# 18-AM64x-07.net
KiCad netlist of a schematic drawn in Altium Designer
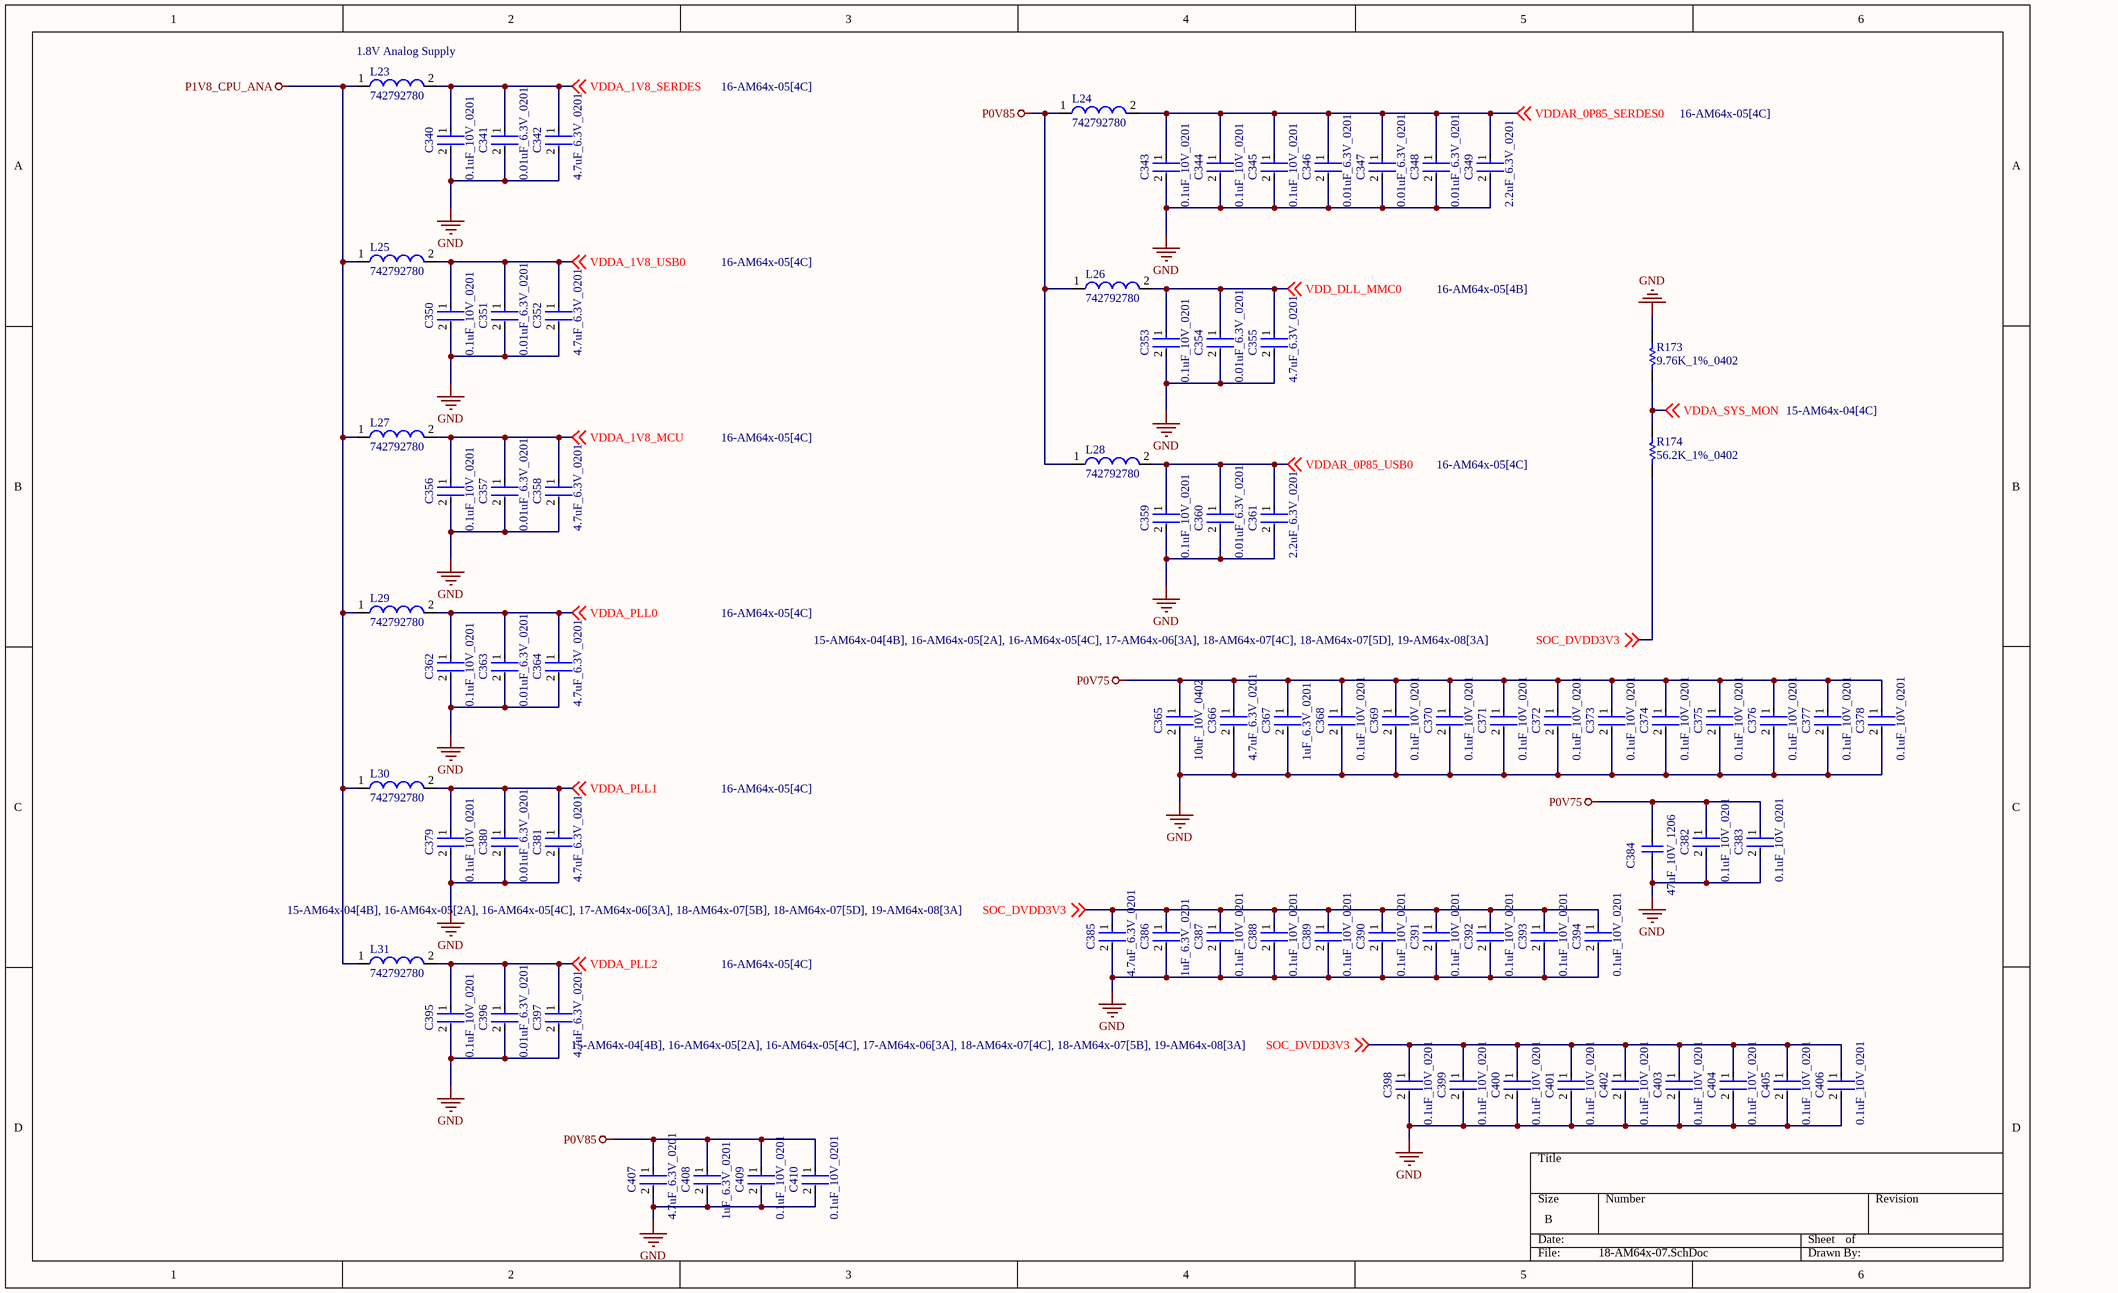
[diagram p0: 18-AM64x-07.SchDoc]

(export (version "E")
  (design (tool "Eeschema 10.0.6"))
  (components
    (comp (ref "C340")
      (value "0.1uF_10V_0201")
      (footprint "FP-GRM033-0_03-IPC_C")
      (description "Chip Multilayer Ceramic Capacitors for General Purpose, 0201, 0.10uF, X5R, 15%, 10%, 10V")
      (fields (field (name "TOLERANCE") "10%") (field (name "VOLTAGE") "10V"))
      (libsource (lib "Altium Content Vault") (part "b4654b650e69147ec39a6b967a45e02"))
    )
    (comp (ref "C341")
      (value "0.01uF_6.3V_0201")
      (footprint "FP-GRM033-0_03-IPC_A")
      (description "Chip Multilayer Ceramic Capacitors for General Purpose, 0201, 10000pF, X7R, 15%, 10%, 6.3V")
      (fields (field (name "TOLERANCE") "10%") (field (name "VOLTAGE") "6.3V"))
      (libsource (lib "Altium Content Vault") (part "b4654b650e69147ec39a6b967a45e02"))
    )
    (comp (ref "C342")
      (value "4.7uF_6.3V_0201")
      (footprint "FP-GRM035-0_09-IPC_B")
      (description "Chip Multilayer Ceramic Capacitors for General Purpose, 0201, 4.7uF, X5R, 15%, 20%, 6.3V")
      (fields (field (name "TOLERANCE") "20%"))
      (libsource (lib "Altium Content Vault") (part "02cd4be3c70576c341d710602a673aa"))
    )
    (comp (ref "C343")
      (value "0.1uF_10V_0201")
      (footprint "FP-GRM033-0_03-IPC_C")
      (description "Chip Multilayer Ceramic Capacitors for General Purpose, 0201, 0.10uF, X5R, 15%, 10%, 10V")
      (fields (field (name "TOLERANCE") "10%") (field (name "VOLTAGE") "10V"))
      (libsource (lib "Altium Content Vault") (part "b4654b650e69147ec39a6b967a45e02"))
    )
    (comp (ref "C344")
      (value "0.1uF_10V_0201")
      (footprint "FP-GRM033-0_03-IPC_C")
      (description "Chip Multilayer Ceramic Capacitors for General Purpose, 0201, 0.10uF, X5R, 15%, 10%, 10V")
      (fields (field (name "TOLERANCE") "10%") (field (name "VOLTAGE") "10V"))
      (libsource (lib "Altium Content Vault") (part "b4654b650e69147ec39a6b967a45e02"))
    )
    (comp (ref "C345")
      (value "0.1uF_10V_0201")
      (footprint "FP-GRM033-0_03-IPC_C")
      (description "Chip Multilayer Ceramic Capacitors for General Purpose, 0201, 0.10uF, X5R, 15%, 10%, 10V")
      (fields (field (name "TOLERANCE") "10%") (field (name "VOLTAGE") "10V"))
      (libsource (lib "Altium Content Vault") (part "b4654b650e69147ec39a6b967a45e02"))
    )
    (comp (ref "C346")
      (value "0.01uF_6.3V_0201")
      (footprint "FP-GRM033-0_03-IPC_A")
      (description "Chip Multilayer Ceramic Capacitors for General Purpose, 0201, 10000pF, X7R, 15%, 10%, 6.3V")
      (fields (field (name "TOLERANCE") "10%") (field (name "VOLTAGE") "6.3V"))
      (libsource (lib "Altium Content Vault") (part "b4654b650e69147ec39a6b967a45e02"))
    )
    (comp (ref "C347")
      (value "0.01uF_6.3V_0201")
      (footprint "FP-GRM033-0_03-IPC_A")
      (description "Chip Multilayer Ceramic Capacitors for General Purpose, 0201, 10000pF, X7R, 15%, 10%, 6.3V")
      (fields (field (name "TOLERANCE") "10%") (field (name "VOLTAGE") "6.3V"))
      (libsource (lib "Altium Content Vault") (part "b4654b650e69147ec39a6b967a45e02"))
    )
    (comp (ref "C348")
      (value "0.01uF_6.3V_0201")
      (footprint "FP-GRM033-0_03-IPC_A")
      (description "Chip Multilayer Ceramic Capacitors for General Purpose, 0201, 10000pF, X7R, 15%, 10%, 6.3V")
      (fields (field (name "TOLERANCE") "10%") (field (name "VOLTAGE") "6.3V"))
      (libsource (lib "Altium Content Vault") (part "b4654b650e69147ec39a6b967a45e02"))
    )
    (comp (ref "C349")
      (value "2.2uF_6.3V_0201")
      (footprint "FP-CL03-IPC_C")
      (description "Cap Ceramic 2.2uF 6.3V X5R ±20% Pad SMD 0201 +85°C T/R")
      (fields (field (name "TOLERANCE") "20%"))
      (libsource (lib "Altium Content Vault") (part "b4654b650e69147ec39a6b967a45e02"))
    )
    (comp (ref "C350")
      (value "0.1uF_10V_0201")
      (footprint "FP-GRM033-0_03-IPC_C")
      (description "Chip Multilayer Ceramic Capacitors for General Purpose, 0201, 0.10uF, X5R, 15%, 10%, 10V")
      (fields (field (name "TOLERANCE") "10%") (field (name "VOLTAGE") "10V"))
      (libsource (lib "Altium Content Vault") (part "b4654b650e69147ec39a6b967a45e02"))
    )
    (comp (ref "C351")
      (value "0.01uF_6.3V_0201")
      (footprint "FP-GRM033-0_03-IPC_A")
      (description "Chip Multilayer Ceramic Capacitors for General Purpose, 0201, 10000pF, X7R, 15%, 10%, 6.3V")
      (fields (field (name "TOLERANCE") "10%") (field (name "VOLTAGE") "6.3V"))
      (libsource (lib "Altium Content Vault") (part "b4654b650e69147ec39a6b967a45e02"))
    )
    (comp (ref "C352")
      (value "4.7uF_6.3V_0201")
      (footprint "FP-GRM035-0_09-IPC_B")
      (description "Chip Multilayer Ceramic Capacitors for General Purpose, 0201, 4.7uF, X5R, 15%, 20%, 6.3V")
      (fields (field (name "TOLERANCE") "20%"))
      (libsource (lib "Altium Content Vault") (part "02cd4be3c70576c341d710602a673aa"))
    )
    (comp (ref "C353")
      (value "0.1uF_10V_0201")
      (footprint "FP-GRM033-0_03-IPC_C")
      (description "Chip Multilayer Ceramic Capacitors for General Purpose, 0201, 0.10uF, X5R, 15%, 10%, 10V")
      (fields (field (name "TOLERANCE") "10%") (field (name "VOLTAGE") "10V"))
      (libsource (lib "Altium Content Vault") (part "b4654b650e69147ec39a6b967a45e02"))
    )
    (comp (ref "C354")
      (value "0.01uF_6.3V_0201")
      (footprint "FP-GRM033-0_03-IPC_A")
      (description "Chip Multilayer Ceramic Capacitors for General Purpose, 0201, 10000pF, X7R, 15%, 10%, 6.3V")
      (fields (field (name "TOLERANCE") "10%") (field (name "VOLTAGE") "6.3V"))
      (libsource (lib "Altium Content Vault") (part "b4654b650e69147ec39a6b967a45e02"))
    )
    (comp (ref "C355")
      (value "4.7uF_6.3V_0201")
      (footprint "FP-GRM035-0_09-IPC_B")
      (description "Chip Multilayer Ceramic Capacitors for General Purpose, 0201, 4.7uF, X5R, 15%, 20%, 6.3V")
      (fields (field (name "TOLERANCE") "20%"))
      (libsource (lib "Altium Content Vault") (part "02cd4be3c70576c341d710602a673aa"))
    )
    (comp (ref "C356")
      (value "0.1uF_10V_0201")
      (footprint "FP-GRM033-0_03-IPC_C")
      (description "Chip Multilayer Ceramic Capacitors for General Purpose, 0201, 0.10uF, X5R, 15%, 10%, 10V")
      (fields (field (name "TOLERANCE") "10%") (field (name "VOLTAGE") "10V"))
      (libsource (lib "Altium Content Vault") (part "b4654b650e69147ec39a6b967a45e02"))
    )
    (comp (ref "C357")
      (value "0.01uF_6.3V_0201")
      (footprint "FP-GRM033-0_03-IPC_A")
      (description "Chip Multilayer Ceramic Capacitors for General Purpose, 0201, 10000pF, X7R, 15%, 10%, 6.3V")
      (fields (field (name "TOLERANCE") "10%") (field (name "VOLTAGE") "6.3V"))
      (libsource (lib "Altium Content Vault") (part "b4654b650e69147ec39a6b967a45e02"))
    )
    (comp (ref "C358")
      (value "4.7uF_6.3V_0201")
      (footprint "FP-GRM035-0_09-IPC_B")
      (description "Chip Multilayer Ceramic Capacitors for General Purpose, 0201, 4.7uF, X5R, 15%, 20%, 6.3V")
      (fields (field (name "TOLERANCE") "20%"))
      (libsource (lib "Altium Content Vault") (part "02cd4be3c70576c341d710602a673aa"))
    )
    (comp (ref "C359")
      (value "0.1uF_10V_0201")
      (footprint "FP-GRM033-0_03-IPC_C")
      (description "Chip Multilayer Ceramic Capacitors for General Purpose, 0201, 0.10uF, X5R, 15%, 10%, 10V")
      (fields (field (name "TOLERANCE") "10%") (field (name "VOLTAGE") "10V"))
      (libsource (lib "Altium Content Vault") (part "b4654b650e69147ec39a6b967a45e02"))
    )
    (comp (ref "C360")
      (value "0.01uF_6.3V_0201")
      (footprint "FP-GRM033-0_03-IPC_A")
      (description "Chip Multilayer Ceramic Capacitors for General Purpose, 0201, 10000pF, X7R, 15%, 10%, 6.3V")
      (fields (field (name "TOLERANCE") "10%") (field (name "VOLTAGE") "6.3V"))
      (libsource (lib "Altium Content Vault") (part "b4654b650e69147ec39a6b967a45e02"))
    )
    (comp (ref "C361")
      (value "2.2uF_6.3V_0201")
      (footprint "FP-CL03-IPC_C")
      (description "Cap Ceramic 2.2uF 6.3V X5R ±20% Pad SMD 0201 +85°C T/R")
      (fields (field (name "TOLERANCE") "20%"))
      (libsource (lib "Altium Content Vault") (part "b4654b650e69147ec39a6b967a45e02"))
    )
    (comp (ref "C362")
      (value "0.1uF_10V_0201")
      (footprint "FP-GRM033-0_03-IPC_C")
      (description "Chip Multilayer Ceramic Capacitors for General Purpose, 0201, 0.10uF, X5R, 15%, 10%, 10V")
      (fields (field (name "TOLERANCE") "10%") (field (name "VOLTAGE") "10V"))
      (libsource (lib "Altium Content Vault") (part "b4654b650e69147ec39a6b967a45e02"))
    )
    (comp (ref "C363")
      (value "0.01uF_6.3V_0201")
      (footprint "FP-GRM033-0_03-IPC_A")
      (description "Chip Multilayer Ceramic Capacitors for General Purpose, 0201, 10000pF, X7R, 15%, 10%, 6.3V")
      (fields (field (name "TOLERANCE") "10%") (field (name "VOLTAGE") "6.3V"))
      (libsource (lib "Altium Content Vault") (part "b4654b650e69147ec39a6b967a45e02"))
    )
    (comp (ref "C364")
      (value "4.7uF_6.3V_0201")
      (footprint "FP-GRM035-0_09-IPC_B")
      (description "Chip Multilayer Ceramic Capacitors for General Purpose, 0201, 4.7uF, X5R, 15%, 20%, 6.3V")
      (fields (field (name "TOLERANCE") "20%"))
      (libsource (lib "Altium Content Vault") (part "02cd4be3c70576c341d710602a673aa"))
    )
    (comp (ref "C365")
      (value "10uF_10V_0402")
      (footprint "FP-CL05A106MP5NUNC-MFG")
      (description "CAP CER 10UF 10V X5R 0402")
      (fields
        (field (name "OCTOPART") "https://octopart.com/cl05a106mp5nunc-samsung-22457395")
        (field (name "TOLERANCE") "20%")
      )
      (libsource (lib "Altium Content Vault") (part "b4654b650e69147ec39a6b967a45e02"))
    )
    (comp (ref "C366")
      (value "4.7uF_6.3V_0201")
      (footprint "FP-GRM035-0_09-IPC_B")
      (description "Chip Multilayer Ceramic Capacitors for General Purpose, 0201, 4.7uF, X5R, 15%, 20%, 6.3V")
      (fields (field (name "TOLERANCE") "20%"))
      (libsource (lib "Altium Content Vault") (part "02cd4be3c70576c341d710602a673aa"))
    )
    (comp (ref "C367")
      (value "1uF_6.3V_0201")
      (footprint "FP-CL03-IPC_B")
      (description "Cap Ceramic 1uF 6.3V X5R ±20% Pad SMD 0201 +85°C T/R")
      (fields (field (name "TOLERANCE") "20%"))
      (libsource (lib "Altium Content Vault") (part "b4654b650e69147ec39a6b967a45e02"))
    )
    (comp (ref "C368")
      (value "0.1uF_10V_0201")
      (footprint "FP-GRM033-0_03-IPC_C")
      (description "Chip Multilayer Ceramic Capacitors for General Purpose, 0201, 0.10uF, X5R, 15%, 10%, 10V")
      (fields (field (name "TOLERANCE") "10%") (field (name "VOLTAGE") "10V"))
      (libsource (lib "Altium Content Vault") (part "b4654b650e69147ec39a6b967a45e02"))
    )
    (comp (ref "C369")
      (value "0.1uF_10V_0201")
      (footprint "FP-GRM033-0_03-IPC_C")
      (description "Chip Multilayer Ceramic Capacitors for General Purpose, 0201, 0.10uF, X5R, 15%, 10%, 10V")
      (fields (field (name "TOLERANCE") "10%") (field (name "VOLTAGE") "10V"))
      (libsource (lib "Altium Content Vault") (part "b4654b650e69147ec39a6b967a45e02"))
    )
    (comp (ref "C370")
      (value "0.1uF_10V_0201")
      (footprint "FP-GRM033-0_03-IPC_C")
      (description "Chip Multilayer Ceramic Capacitors for General Purpose, 0201, 0.10uF, X5R, 15%, 10%, 10V")
      (fields (field (name "TOLERANCE") "10%") (field (name "VOLTAGE") "10V"))
      (libsource (lib "Altium Content Vault") (part "b4654b650e69147ec39a6b967a45e02"))
    )
    (comp (ref "C371")
      (value "0.1uF_10V_0201")
      (footprint "FP-GRM033-0_03-IPC_C")
      (description "Chip Multilayer Ceramic Capacitors for General Purpose, 0201, 0.10uF, X5R, 15%, 10%, 10V")
      (fields (field (name "TOLERANCE") "10%") (field (name "VOLTAGE") "10V"))
      (libsource (lib "Altium Content Vault") (part "b4654b650e69147ec39a6b967a45e02"))
    )
    (comp (ref "C372")
      (value "0.1uF_10V_0201")
      (footprint "FP-GRM033-0_03-IPC_C")
      (description "Chip Multilayer Ceramic Capacitors for General Purpose, 0201, 0.10uF, X5R, 15%, 10%, 10V")
      (fields (field (name "TOLERANCE") "10%") (field (name "VOLTAGE") "10V"))
      (libsource (lib "Altium Content Vault") (part "b4654b650e69147ec39a6b967a45e02"))
    )
    (comp (ref "C373")
      (value "0.1uF_10V_0201")
      (footprint "FP-GRM033-0_03-IPC_C")
      (description "Chip Multilayer Ceramic Capacitors for General Purpose, 0201, 0.10uF, X5R, 15%, 10%, 10V")
      (fields (field (name "TOLERANCE") "10%") (field (name "VOLTAGE") "10V"))
      (libsource (lib "Altium Content Vault") (part "b4654b650e69147ec39a6b967a45e02"))
    )
    (comp (ref "C374")
      (value "0.1uF_10V_0201")
      (footprint "FP-GRM033-0_03-IPC_C")
      (description "Chip Multilayer Ceramic Capacitors for General Purpose, 0201, 0.10uF, X5R, 15%, 10%, 10V")
      (fields (field (name "TOLERANCE") "10%") (field (name "VOLTAGE") "10V"))
      (libsource (lib "Altium Content Vault") (part "b4654b650e69147ec39a6b967a45e02"))
    )
    (comp (ref "C375")
      (value "0.1uF_10V_0201")
      (footprint "FP-GRM033-0_03-IPC_C")
      (description "Chip Multilayer Ceramic Capacitors for General Purpose, 0201, 0.10uF, X5R, 15%, 10%, 10V")
      (fields (field (name "TOLERANCE") "10%") (field (name "VOLTAGE") "10V"))
      (libsource (lib "Altium Content Vault") (part "b4654b650e69147ec39a6b967a45e02"))
    )
    (comp (ref "C376")
      (value "0.1uF_10V_0201")
      (footprint "FP-GRM033-0_03-IPC_C")
      (description "Chip Multilayer Ceramic Capacitors for General Purpose, 0201, 0.10uF, X5R, 15%, 10%, 10V")
      (fields (field (name "TOLERANCE") "10%") (field (name "VOLTAGE") "10V"))
      (libsource (lib "Altium Content Vault") (part "b4654b650e69147ec39a6b967a45e02"))
    )
    (comp (ref "C377")
      (value "0.1uF_10V_0201")
      (footprint "FP-GRM033-0_03-IPC_C")
      (description "Chip Multilayer Ceramic Capacitors for General Purpose, 0201, 0.10uF, X5R, 15%, 10%, 10V")
      (fields (field (name "TOLERANCE") "10%") (field (name "VOLTAGE") "10V"))
      (libsource (lib "Altium Content Vault") (part "b4654b650e69147ec39a6b967a45e02"))
    )
    (comp (ref "C378")
      (value "0.1uF_10V_0201")
      (footprint "FP-GRM033-0_03-IPC_C")
      (description "Chip Multilayer Ceramic Capacitors for General Purpose, 0201, 0.10uF, X5R, 15%, 10%, 10V")
      (fields (field (name "TOLERANCE") "10%") (field (name "VOLTAGE") "10V"))
      (libsource (lib "Altium Content Vault") (part "b4654b650e69147ec39a6b967a45e02"))
    )
    (comp (ref "C379")
      (value "0.1uF_10V_0201")
      (footprint "FP-GRM033-0_03-IPC_C")
      (description "Chip Multilayer Ceramic Capacitors for General Purpose, 0201, 0.10uF, X5R, 15%, 10%, 10V")
      (fields (field (name "TOLERANCE") "10%") (field (name "VOLTAGE") "10V"))
      (libsource (lib "Altium Content Vault") (part "b4654b650e69147ec39a6b967a45e02"))
    )
    (comp (ref "C380")
      (value "0.01uF_6.3V_0201")
      (footprint "FP-GRM033-0_03-IPC_A")
      (description "Chip Multilayer Ceramic Capacitors for General Purpose, 0201, 10000pF, X7R, 15%, 10%, 6.3V")
      (fields (field (name "TOLERANCE") "10%") (field (name "VOLTAGE") "6.3V"))
      (libsource (lib "Altium Content Vault") (part "b4654b650e69147ec39a6b967a45e02"))
    )
    (comp (ref "C381")
      (value "4.7uF_6.3V_0201")
      (footprint "FP-GRM035-0_09-IPC_B")
      (description "Chip Multilayer Ceramic Capacitors for General Purpose, 0201, 4.7uF, X5R, 15%, 20%, 6.3V")
      (fields (field (name "TOLERANCE") "20%"))
      (libsource (lib "Altium Content Vault") (part "02cd4be3c70576c341d710602a673aa"))
    )
    (comp (ref "C382")
      (value "0.1uF_10V_0201")
      (footprint "FP-GRM033-0_03-IPC_C")
      (description "Chip Multilayer Ceramic Capacitors for General Purpose, 0201, 0.10uF, X5R, 15%, 10%, 10V")
      (fields (field (name "TOLERANCE") "10%") (field (name "VOLTAGE") "10V"))
      (libsource (lib "Altium Content Vault") (part "b4654b650e69147ec39a6b967a45e02"))
    )
    (comp (ref "C383")
      (value "0.1uF_10V_0201")
      (footprint "FP-GRM033-0_03-IPC_C")
      (description "Chip Multilayer Ceramic Capacitors for General Purpose, 0201, 0.10uF, X5R, 15%, 10%, 10V")
      (fields (field (name "TOLERANCE") "10%") (field (name "VOLTAGE") "10V"))
      (libsource (lib "Altium Content Vault") (part "b4654b650e69147ec39a6b967a45e02"))
    )
    (comp (ref "C384")
      (value "47uF_10V_1206")
      (footprint "CAPC1206(3216)190_N")
      (description "CAP 47uF 10V ±20% 1206 (3216 Metric) Thickness 1.9mm SMD")
      (fields (field (name "TOLERANCE") "Â±20%"))
      (libsource (lib "Altium Content Vault") (part "CAP"))
    )
    (comp (ref "C385")
      (value "4.7uF_6.3V_0201")
      (footprint "FP-GRM035-0_09-IPC_B")
      (description "Chip Multilayer Ceramic Capacitors for General Purpose, 0201, 4.7uF, X5R, 15%, 20%, 6.3V")
      (fields (field (name "TOLERANCE") "20%"))
      (libsource (lib "Altium Content Vault") (part "02cd4be3c70576c341d710602a673aa"))
    )
    (comp (ref "C386")
      (value "1uF_6.3V_0201")
      (footprint "FP-CL03-IPC_B")
      (description "Cap Ceramic 1uF 6.3V X5R ±20% Pad SMD 0201 +85°C T/R")
      (fields (field (name "TOLERANCE") "20%"))
      (libsource (lib "Altium Content Vault") (part "b4654b650e69147ec39a6b967a45e02"))
    )
    (comp (ref "C387")
      (value "0.1uF_10V_0201")
      (footprint "FP-GRM033-0_03-IPC_C")
      (description "Chip Multilayer Ceramic Capacitors for General Purpose, 0201, 0.10uF, X5R, 15%, 10%, 10V")
      (fields (field (name "TOLERANCE") "10%") (field (name "VOLTAGE") "10V"))
      (libsource (lib "Altium Content Vault") (part "b4654b650e69147ec39a6b967a45e02"))
    )
    (comp (ref "C388")
      (value "0.1uF_10V_0201")
      (footprint "FP-GRM033-0_03-IPC_C")
      (description "Chip Multilayer Ceramic Capacitors for General Purpose, 0201, 0.10uF, X5R, 15%, 10%, 10V")
      (fields (field (name "TOLERANCE") "10%") (field (name "VOLTAGE") "10V"))
      (libsource (lib "Altium Content Vault") (part "b4654b650e69147ec39a6b967a45e02"))
    )
    (comp (ref "C389")
      (value "0.1uF_10V_0201")
      (footprint "FP-GRM033-0_03-IPC_C")
      (description "Chip Multilayer Ceramic Capacitors for General Purpose, 0201, 0.10uF, X5R, 15%, 10%, 10V")
      (fields (field (name "TOLERANCE") "10%") (field (name "VOLTAGE") "10V"))
      (libsource (lib "Altium Content Vault") (part "b4654b650e69147ec39a6b967a45e02"))
    )
    (comp (ref "C390")
      (value "0.1uF_10V_0201")
      (footprint "FP-GRM033-0_03-IPC_C")
      (description "Chip Multilayer Ceramic Capacitors for General Purpose, 0201, 0.10uF, X5R, 15%, 10%, 10V")
      (fields (field (name "TOLERANCE") "10%") (field (name "VOLTAGE") "10V"))
      (libsource (lib "Altium Content Vault") (part "b4654b650e69147ec39a6b967a45e02"))
    )
    (comp (ref "C391")
      (value "0.1uF_10V_0201")
      (footprint "FP-GRM033-0_03-IPC_C")
      (description "Chip Multilayer Ceramic Capacitors for General Purpose, 0201, 0.10uF, X5R, 15%, 10%, 10V")
      (fields (field (name "TOLERANCE") "10%") (field (name "VOLTAGE") "10V"))
      (libsource (lib "Altium Content Vault") (part "b4654b650e69147ec39a6b967a45e02"))
    )
    (comp (ref "C392")
      (value "0.1uF_10V_0201")
      (footprint "FP-GRM033-0_03-IPC_C")
      (description "Chip Multilayer Ceramic Capacitors for General Purpose, 0201, 0.10uF, X5R, 15%, 10%, 10V")
      (fields (field (name "TOLERANCE") "10%") (field (name "VOLTAGE") "10V"))
      (libsource (lib "Altium Content Vault") (part "b4654b650e69147ec39a6b967a45e02"))
    )
    (comp (ref "C393")
      (value "0.1uF_10V_0201")
      (footprint "FP-GRM033-0_03-IPC_C")
      (description "Chip Multilayer Ceramic Capacitors for General Purpose, 0201, 0.10uF, X5R, 15%, 10%, 10V")
      (fields (field (name "TOLERANCE") "10%") (field (name "VOLTAGE") "10V"))
      (libsource (lib "Altium Content Vault") (part "b4654b650e69147ec39a6b967a45e02"))
    )
    (comp (ref "C394")
      (value "0.1uF_10V_0201")
      (footprint "FP-GRM033-0_03-IPC_C")
      (description "Chip Multilayer Ceramic Capacitors for General Purpose, 0201, 0.10uF, X5R, 15%, 10%, 10V")
      (fields (field (name "TOLERANCE") "10%") (field (name "VOLTAGE") "10V"))
      (libsource (lib "Altium Content Vault") (part "b4654b650e69147ec39a6b967a45e02"))
    )
    (comp (ref "C395")
      (value "0.1uF_10V_0201")
      (footprint "FP-GRM033-0_03-IPC_C")
      (description "Chip Multilayer Ceramic Capacitors for General Purpose, 0201, 0.10uF, X5R, 15%, 10%, 10V")
      (fields (field (name "TOLERANCE") "10%") (field (name "VOLTAGE") "10V"))
      (libsource (lib "Altium Content Vault") (part "b4654b650e69147ec39a6b967a45e02"))
    )
    (comp (ref "C396")
      (value "0.01uF_6.3V_0201")
      (footprint "FP-GRM033-0_03-IPC_A")
      (description "Chip Multilayer Ceramic Capacitors for General Purpose, 0201, 10000pF, X7R, 15%, 10%, 6.3V")
      (fields (field (name "TOLERANCE") "10%") (field (name "VOLTAGE") "6.3V"))
      (libsource (lib "Altium Content Vault") (part "b4654b650e69147ec39a6b967a45e02"))
    )
    (comp (ref "C397")
      (value "4.7uF_6.3V_0201")
      (footprint "FP-GRM035-0_09-IPC_B")
      (description "Chip Multilayer Ceramic Capacitors for General Purpose, 0201, 4.7uF, X5R, 15%, 20%, 6.3V")
      (fields (field (name "TOLERANCE") "20%"))
      (libsource (lib "Altium Content Vault") (part "02cd4be3c70576c341d710602a673aa"))
    )
    (comp (ref "C398")
      (value "0.1uF_10V_0201")
      (footprint "FP-GRM033-0_03-IPC_C")
      (description "Chip Multilayer Ceramic Capacitors for General Purpose, 0201, 0.10uF, X5R, 15%, 10%, 10V")
      (fields (field (name "TOLERANCE") "10%") (field (name "VOLTAGE") "10V"))
      (libsource (lib "Altium Content Vault") (part "b4654b650e69147ec39a6b967a45e02"))
    )
    (comp (ref "C399")
      (value "0.1uF_10V_0201")
      (footprint "FP-GRM033-0_03-IPC_C")
      (description "Chip Multilayer Ceramic Capacitors for General Purpose, 0201, 0.10uF, X5R, 15%, 10%, 10V")
      (fields (field (name "TOLERANCE") "10%") (field (name "VOLTAGE") "10V"))
      (libsource (lib "Altium Content Vault") (part "b4654b650e69147ec39a6b967a45e02"))
    )
    (comp (ref "C400")
      (value "0.1uF_10V_0201")
      (footprint "FP-GRM033-0_03-IPC_C")
      (description "Chip Multilayer Ceramic Capacitors for General Purpose, 0201, 0.10uF, X5R, 15%, 10%, 10V")
      (fields (field (name "TOLERANCE") "10%") (field (name "VOLTAGE") "10V"))
      (libsource (lib "Altium Content Vault") (part "b4654b650e69147ec39a6b967a45e02"))
    )
    (comp (ref "C401")
      (value "0.1uF_10V_0201")
      (footprint "FP-GRM033-0_03-IPC_C")
      (description "Chip Multilayer Ceramic Capacitors for General Purpose, 0201, 0.10uF, X5R, 15%, 10%, 10V")
      (fields (field (name "TOLERANCE") "10%") (field (name "VOLTAGE") "10V"))
      (libsource (lib "Altium Content Vault") (part "b4654b650e69147ec39a6b967a45e02"))
    )
    (comp (ref "C402")
      (value "0.1uF_10V_0201")
      (footprint "FP-GRM033-0_03-IPC_C")
      (description "Chip Multilayer Ceramic Capacitors for General Purpose, 0201, 0.10uF, X5R, 15%, 10%, 10V")
      (fields (field (name "TOLERANCE") "10%") (field (name "VOLTAGE") "10V"))
      (libsource (lib "Altium Content Vault") (part "b4654b650e69147ec39a6b967a45e02"))
    )
    (comp (ref "C403")
      (value "0.1uF_10V_0201")
      (footprint "FP-GRM033-0_03-IPC_C")
      (description "Chip Multilayer Ceramic Capacitors for General Purpose, 0201, 0.10uF, X5R, 15%, 10%, 10V")
      (fields (field (name "TOLERANCE") "10%") (field (name "VOLTAGE") "10V"))
      (libsource (lib "Altium Content Vault") (part "b4654b650e69147ec39a6b967a45e02"))
    )
    (comp (ref "C404")
      (value "0.1uF_10V_0201")
      (footprint "FP-GRM033-0_03-IPC_C")
      (description "Chip Multilayer Ceramic Capacitors for General Purpose, 0201, 0.10uF, X5R, 15%, 10%, 10V")
      (fields (field (name "TOLERANCE") "10%") (field (name "VOLTAGE") "10V"))
      (libsource (lib "Altium Content Vault") (part "b4654b650e69147ec39a6b967a45e02"))
    )
    (comp (ref "C405")
      (value "0.1uF_10V_0201")
      (footprint "FP-GRM033-0_03-IPC_C")
      (description "Chip Multilayer Ceramic Capacitors for General Purpose, 0201, 0.10uF, X5R, 15%, 10%, 10V")
      (fields (field (name "TOLERANCE") "10%") (field (name "VOLTAGE") "10V"))
      (libsource (lib "Altium Content Vault") (part "b4654b650e69147ec39a6b967a45e02"))
    )
    (comp (ref "C406")
      (value "0.1uF_10V_0201")
      (footprint "FP-GRM033-0_03-IPC_C")
      (description "Chip Multilayer Ceramic Capacitors for General Purpose, 0201, 0.10uF, X5R, 15%, 10%, 10V")
      (fields (field (name "TOLERANCE") "10%") (field (name "VOLTAGE") "10V"))
      (libsource (lib "Altium Content Vault") (part "b4654b650e69147ec39a6b967a45e02"))
    )
    (comp (ref "C407")
      (value "4.7uF_6.3V_0201")
      (footprint "FP-GRM035-0_09-IPC_B")
      (description "Chip Multilayer Ceramic Capacitors for General Purpose, 0201, 4.7uF, X5R, 15%, 20%, 6.3V")
      (fields (field (name "TOLERANCE") "20%"))
      (libsource (lib "Altium Content Vault") (part "02cd4be3c70576c341d710602a673aa"))
    )
    (comp (ref "C408")
      (value "1uF_6.3V_0201")
      (footprint "FP-CL03-IPC_B")
      (description "Cap Ceramic 1uF 6.3V X5R ±20% Pad SMD 0201 +85°C T/R")
      (fields (field (name "TOLERANCE") "20%"))
      (libsource (lib "Altium Content Vault") (part "b4654b650e69147ec39a6b967a45e02"))
    )
    (comp (ref "C409")
      (value "0.1uF_10V_0201")
      (footprint "FP-GRM033-0_03-IPC_C")
      (description "Chip Multilayer Ceramic Capacitors for General Purpose, 0201, 0.10uF, X5R, 15%, 10%, 10V")
      (fields (field (name "TOLERANCE") "10%") (field (name "VOLTAGE") "10V"))
      (libsource (lib "Altium Content Vault") (part "b4654b650e69147ec39a6b967a45e02"))
    )
    (comp (ref "C410")
      (value "0.1uF_10V_0201")
      (footprint "FP-GRM033-0_03-IPC_C")
      (description "Chip Multilayer Ceramic Capacitors for General Purpose, 0201, 0.10uF, X5R, 15%, 10%, 10V")
      (fields (field (name "TOLERANCE") "10%") (field (name "VOLTAGE") "10V"))
      (libsource (lib "Altium Content Vault") (part "b4654b650e69147ec39a6b967a45e02"))
    )
    (comp (ref "L23")
      (value "742792780")
      (footprint "SMD-0402")
      (description "SMD EMI Suppression Ferrite Bead WE-CBF, Z = 220 Ohm")
      (libsource (lib "Altium Content Vault") (part "PAS-IND-INDUCTOR-2"))
    )
    (comp (ref "L24")
      (value "742792780")
      (footprint "SMD-0402")
      (description "SMD EMI Suppression Ferrite Bead WE-CBF, Z = 220 Ohm")
      (libsource (lib "Altium Content Vault") (part "PAS-IND-INDUCTOR-2"))
    )
    (comp (ref "L25")
      (value "742792780")
      (footprint "SMD-0402")
      (description "SMD EMI Suppression Ferrite Bead WE-CBF, Z = 220 Ohm")
      (libsource (lib "Altium Content Vault") (part "PAS-IND-INDUCTOR-2"))
    )
    (comp (ref "L26")
      (value "742792780")
      (footprint "SMD-0402")
      (description "SMD EMI Suppression Ferrite Bead WE-CBF, Z = 220 Ohm")
      (libsource (lib "Altium Content Vault") (part "PAS-IND-INDUCTOR-2"))
    )
    (comp (ref "L27")
      (value "742792780")
      (footprint "SMD-0402")
      (description "SMD EMI Suppression Ferrite Bead WE-CBF, Z = 220 Ohm")
      (libsource (lib "Altium Content Vault") (part "PAS-IND-INDUCTOR-2"))
    )
    (comp (ref "L28")
      (value "742792780")
      (footprint "SMD-0402")
      (description "SMD EMI Suppression Ferrite Bead WE-CBF, Z = 220 Ohm")
      (libsource (lib "Altium Content Vault") (part "PAS-IND-INDUCTOR-2"))
    )
    (comp (ref "L29")
      (value "742792780")
      (footprint "SMD-0402")
      (description "SMD EMI Suppression Ferrite Bead WE-CBF, Z = 220 Ohm")
      (libsource (lib "Altium Content Vault") (part "PAS-IND-INDUCTOR-2"))
    )
    (comp (ref "L30")
      (value "742792780")
      (footprint "SMD-0402")
      (description "SMD EMI Suppression Ferrite Bead WE-CBF, Z = 220 Ohm")
      (libsource (lib "Altium Content Vault") (part "PAS-IND-INDUCTOR-2"))
    )
    (comp (ref "L31")
      (value "742792780")
      (footprint "SMD-0402")
      (description "SMD EMI Suppression Ferrite Bead WE-CBF, Z = 220 Ohm")
      (libsource (lib "Altium Content Vault") (part "PAS-IND-INDUCTOR-2"))
    )
    (comp (ref "R173")
      (value "9.76K_1%_0402")
      (footprint "RESC1005X40X25NL05T10")
      (fields (field (name "PART NUMBER") "RC0402FR-079K76L") (field (name "MANUFACTURER") "Yageo / Phycomp"))
      (libsource (lib "Altium Content Vault") (part "RES"))
    )
    (comp (ref "R174")
      (value "56.2K_1%_0402")
      (footprint "RESC1005X40X25LL05T05")
      (fields (field (name "PART NUMBER") "ERJ-2RKF5622X") (field (name "MANUFACTURER") "Panasonic"))
      (libsource (lib "Altium Content Vault") (part "RES"))
    )
  )
  (nets
    (net (code "1") (name "GND") (class "Default")
      (node (ref "C340") (pin "2") (pinfunction "2_2") (pintype "passive"))
      (node (ref "C341") (pin "2") (pinfunction "2_2") (pintype "passive"))
      (node (ref "C342") (pin "2") (pinfunction "2_2") (pintype "passive"))
      (node (ref "C343") (pin "2") (pinfunction "2_2") (pintype "passive"))
      (node (ref "C344") (pin "2") (pinfunction "2_2") (pintype "passive"))
      (node (ref "C345") (pin "2") (pinfunction "2_2") (pintype "passive"))
      (node (ref "C346") (pin "2") (pinfunction "2_2") (pintype "passive"))
      (node (ref "C347") (pin "2") (pinfunction "2_2") (pintype "passive"))
      (node (ref "C348") (pin "2") (pinfunction "2_2") (pintype "passive"))
      (node (ref "C349") (pin "2") (pinfunction "2_2") (pintype "passive"))
      (node (ref "C350") (pin "2") (pinfunction "2_2") (pintype "passive"))
      (node (ref "C351") (pin "2") (pinfunction "2_2") (pintype "passive"))
      (node (ref "C352") (pin "2") (pinfunction "2_2") (pintype "passive"))
      (node (ref "C353") (pin "2") (pinfunction "2_2") (pintype "passive"))
      (node (ref "C354") (pin "2") (pinfunction "2_2") (pintype "passive"))
      (node (ref "C355") (pin "2") (pinfunction "2_2") (pintype "passive"))
      (node (ref "C356") (pin "2") (pinfunction "2_2") (pintype "passive"))
      (node (ref "C357") (pin "2") (pinfunction "2_2") (pintype "passive"))
      (node (ref "C358") (pin "2") (pinfunction "2_2") (pintype "passive"))
      (node (ref "C359") (pin "2") (pinfunction "2_2") (pintype "passive"))
      (node (ref "C360") (pin "2") (pinfunction "2_2") (pintype "passive"))
      (node (ref "C361") (pin "2") (pinfunction "2_2") (pintype "passive"))
      (node (ref "C362") (pin "2") (pinfunction "2_2") (pintype "passive"))
      (node (ref "C363") (pin "2") (pinfunction "2_2") (pintype "passive"))
      (node (ref "C364") (pin "2") (pinfunction "2_2") (pintype "passive"))
      (node (ref "C365") (pin "2") (pinfunction "2_2") (pintype "passive"))
      (node (ref "C366") (pin "2") (pinfunction "2_2") (pintype "passive"))
      (node (ref "C367") (pin "2") (pinfunction "2_2") (pintype "passive"))
      (node (ref "C368") (pin "2") (pinfunction "2_2") (pintype "passive"))
      (node (ref "C369") (pin "2") (pinfunction "2_2") (pintype "passive"))
      (node (ref "C370") (pin "2") (pinfunction "2_2") (pintype "passive"))
      (node (ref "C371") (pin "2") (pinfunction "2_2") (pintype "passive"))
      (node (ref "C372") (pin "2") (pinfunction "2_2") (pintype "passive"))
      (node (ref "C373") (pin "2") (pinfunction "2_2") (pintype "passive"))
      (node (ref "C374") (pin "2") (pinfunction "2_2") (pintype "passive"))
      (node (ref "C375") (pin "2") (pinfunction "2_2") (pintype "passive"))
      (node (ref "C376") (pin "2") (pinfunction "2_2") (pintype "passive"))
      (node (ref "C377") (pin "2") (pinfunction "2_2") (pintype "passive"))
      (node (ref "C378") (pin "2") (pinfunction "2_2") (pintype "passive"))
      (node (ref "C379") (pin "2") (pinfunction "2_2") (pintype "passive"))
      (node (ref "C380") (pin "2") (pinfunction "2_2") (pintype "passive"))
      (node (ref "C381") (pin "2") (pinfunction "2_2") (pintype "passive"))
      (node (ref "C382") (pin "2") (pinfunction "2_2") (pintype "passive"))
      (node (ref "C383") (pin "2") (pinfunction "2_2") (pintype "passive"))
      (node (ref "C384") (pin "1") (pinfunction "1_1") (pintype "passive"))
      (node (ref "C385") (pin "2") (pinfunction "2_2") (pintype "passive"))
      (node (ref "C386") (pin "2") (pinfunction "2_2") (pintype "passive"))
      (node (ref "C387") (pin "2") (pinfunction "2_2") (pintype "passive"))
      (node (ref "C388") (pin "2") (pinfunction "2_2") (pintype "passive"))
      (node (ref "C389") (pin "2") (pinfunction "2_2") (pintype "passive"))
      (node (ref "C390") (pin "2") (pinfunction "2_2") (pintype "passive"))
      (node (ref "C391") (pin "2") (pinfunction "2_2") (pintype "passive"))
      (node (ref "C392") (pin "2") (pinfunction "2_2") (pintype "passive"))
      (node (ref "C393") (pin "2") (pinfunction "2_2") (pintype "passive"))
      (node (ref "C394") (pin "2") (pinfunction "2_2") (pintype "passive"))
      (node (ref "C395") (pin "2") (pinfunction "2_2") (pintype "passive"))
      (node (ref "C396") (pin "2") (pinfunction "2_2") (pintype "passive"))
      (node (ref "C397") (pin "2") (pinfunction "2_2") (pintype "passive"))
      (node (ref "C398") (pin "2") (pinfunction "2_2") (pintype "passive"))
      (node (ref "C399") (pin "2") (pinfunction "2_2") (pintype "passive"))
      (node (ref "C400") (pin "2") (pinfunction "2_2") (pintype "passive"))
      (node (ref "C401") (pin "2") (pinfunction "2_2") (pintype "passive"))
      (node (ref "C402") (pin "2") (pinfunction "2_2") (pintype "passive"))
      (node (ref "C403") (pin "2") (pinfunction "2_2") (pintype "passive"))
      (node (ref "C404") (pin "2") (pinfunction "2_2") (pintype "passive"))
      (node (ref "C405") (pin "2") (pinfunction "2_2") (pintype "passive"))
      (node (ref "C406") (pin "2") (pinfunction "2_2") (pintype "passive"))
      (node (ref "C407") (pin "2") (pinfunction "2_2") (pintype "passive"))
      (node (ref "C408") (pin "2") (pinfunction "2_2") (pintype "passive"))
      (node (ref "C409") (pin "2") (pinfunction "2_2") (pintype "passive"))
      (node (ref "C410") (pin "2") (pinfunction "2_2") (pintype "passive"))
      (node (ref "R173") (pin "1") (pinfunction "1_1") (pintype "passive"))
    )
    (net (code "2") (name "P0V75") (class "Default")
      (node (ref "C365") (pin "1") (pinfunction "1_1") (pintype "passive"))
      (node (ref "C366") (pin "1") (pinfunction "1_1") (pintype "passive"))
      (node (ref "C367") (pin "1") (pinfunction "1_1") (pintype "passive"))
      (node (ref "C368") (pin "1") (pinfunction "1_1") (pintype "passive"))
      (node (ref "C369") (pin "1") (pinfunction "1_1") (pintype "passive"))
      (node (ref "C370") (pin "1") (pinfunction "1_1") (pintype "passive"))
      (node (ref "C371") (pin "1") (pinfunction "1_1") (pintype "passive"))
      (node (ref "C372") (pin "1") (pinfunction "1_1") (pintype "passive"))
      (node (ref "C373") (pin "1") (pinfunction "1_1") (pintype "passive"))
      (node (ref "C374") (pin "1") (pinfunction "1_1") (pintype "passive"))
      (node (ref "C375") (pin "1") (pinfunction "1_1") (pintype "passive"))
      (node (ref "C376") (pin "1") (pinfunction "1_1") (pintype "passive"))
      (node (ref "C377") (pin "1") (pinfunction "1_1") (pintype "passive"))
      (node (ref "C378") (pin "1") (pinfunction "1_1") (pintype "passive"))
      (node (ref "C382") (pin "1") (pinfunction "1_1") (pintype "passive"))
      (node (ref "C383") (pin "1") (pinfunction "1_1") (pintype "passive"))
      (node (ref "C384") (pin "2") (pinfunction "2_2") (pintype "passive"))
    )
    (net (code "3") (name "P0V85") (class "Default")
      (node (ref "C407") (pin "1") (pinfunction "1_1") (pintype "passive"))
      (node (ref "C408") (pin "1") (pinfunction "1_1") (pintype "passive"))
      (node (ref "C409") (pin "1") (pinfunction "1_1") (pintype "passive"))
      (node (ref "C410") (pin "1") (pinfunction "1_1") (pintype "passive"))
      (node (ref "L24") (pin "1") (pinfunction "1_1") (pintype "passive"))
      (node (ref "L26") (pin "1") (pinfunction "1_1") (pintype "passive"))
      (node (ref "L28") (pin "1") (pinfunction "1_1") (pintype "passive"))
    )
    (net (code "4") (name "P1V8_CPU_ANA") (class "Default")
      (node (ref "L23") (pin "1") (pinfunction "1_1") (pintype "passive"))
      (node (ref "L25") (pin "1") (pinfunction "1_1") (pintype "passive"))
      (node (ref "L27") (pin "1") (pinfunction "1_1") (pintype "passive"))
      (node (ref "L29") (pin "1") (pinfunction "1_1") (pintype "passive"))
      (node (ref "L30") (pin "1") (pinfunction "1_1") (pintype "passive"))
      (node (ref "L31") (pin "1") (pinfunction "1_1") (pintype "passive"))
    )
    (net (code "5") (name "SOC_DVDD3V3") (class "Default")
      (node (ref "C385") (pin "1") (pinfunction "1_1") (pintype "passive"))
      (node (ref "C386") (pin "1") (pinfunction "1_1") (pintype "passive"))
      (node (ref "C387") (pin "1") (pinfunction "1_1") (pintype "passive"))
      (node (ref "C388") (pin "1") (pinfunction "1_1") (pintype "passive"))
      (node (ref "C389") (pin "1") (pinfunction "1_1") (pintype "passive"))
      (node (ref "C390") (pin "1") (pinfunction "1_1") (pintype "passive"))
      (node (ref "C391") (pin "1") (pinfunction "1_1") (pintype "passive"))
      (node (ref "C392") (pin "1") (pinfunction "1_1") (pintype "passive"))
      (node (ref "C393") (pin "1") (pinfunction "1_1") (pintype "passive"))
      (node (ref "C394") (pin "1") (pinfunction "1_1") (pintype "passive"))
      (node (ref "C398") (pin "1") (pinfunction "1_1") (pintype "passive"))
      (node (ref "C399") (pin "1") (pinfunction "1_1") (pintype "passive"))
      (node (ref "C400") (pin "1") (pinfunction "1_1") (pintype "passive"))
      (node (ref "C401") (pin "1") (pinfunction "1_1") (pintype "passive"))
      (node (ref "C402") (pin "1") (pinfunction "1_1") (pintype "passive"))
      (node (ref "C403") (pin "1") (pinfunction "1_1") (pintype "passive"))
      (node (ref "C404") (pin "1") (pinfunction "1_1") (pintype "passive"))
      (node (ref "C405") (pin "1") (pinfunction "1_1") (pintype "passive"))
      (node (ref "C406") (pin "1") (pinfunction "1_1") (pintype "passive"))
      (node (ref "R174") (pin "2") (pinfunction "2_2") (pintype "passive"))
    )
    (net (code "6") (name "VDDAR_0P85_SERDES0") (class "Default")
      (node (ref "C343") (pin "1") (pinfunction "1_1") (pintype "passive"))
      (node (ref "C344") (pin "1") (pinfunction "1_1") (pintype "passive"))
      (node (ref "C345") (pin "1") (pinfunction "1_1") (pintype "passive"))
      (node (ref "C346") (pin "1") (pinfunction "1_1") (pintype "passive"))
      (node (ref "C347") (pin "1") (pinfunction "1_1") (pintype "passive"))
      (node (ref "C348") (pin "1") (pinfunction "1_1") (pintype "passive"))
      (node (ref "C349") (pin "1") (pinfunction "1_1") (pintype "passive"))
      (node (ref "L24") (pin "2") (pinfunction "2_2") (pintype "passive"))
    )
    (net (code "7") (name "VDDAR_0P85_USB0") (class "Default")
      (node (ref "C359") (pin "1") (pinfunction "1_1") (pintype "passive"))
      (node (ref "C360") (pin "1") (pinfunction "1_1") (pintype "passive"))
      (node (ref "C361") (pin "1") (pinfunction "1_1") (pintype "passive"))
      (node (ref "L28") (pin "2") (pinfunction "2_2") (pintype "passive"))
    )
    (net (code "8") (name "VDDA_1V8_MCU") (class "Default")
      (node (ref "C356") (pin "1") (pinfunction "1_1") (pintype "passive"))
      (node (ref "C357") (pin "1") (pinfunction "1_1") (pintype "passive"))
      (node (ref "C358") (pin "1") (pinfunction "1_1") (pintype "passive"))
      (node (ref "L27") (pin "2") (pinfunction "2_2") (pintype "passive"))
    )
    (net (code "9") (name "VDDA_1V8_SERDES") (class "Default")
      (node (ref "C340") (pin "1") (pinfunction "1_1") (pintype "passive"))
      (node (ref "C341") (pin "1") (pinfunction "1_1") (pintype "passive"))
      (node (ref "C342") (pin "1") (pinfunction "1_1") (pintype "passive"))
      (node (ref "L23") (pin "2") (pinfunction "2_2") (pintype "passive"))
    )
    (net (code "10") (name "VDDA_1V8_USB0") (class "Default")
      (node (ref "C350") (pin "1") (pinfunction "1_1") (pintype "passive"))
      (node (ref "C351") (pin "1") (pinfunction "1_1") (pintype "passive"))
      (node (ref "C352") (pin "1") (pinfunction "1_1") (pintype "passive"))
      (node (ref "L25") (pin "2") (pinfunction "2_2") (pintype "passive"))
    )
    (net (code "11") (name "VDDA_PLL0") (class "Default")
      (node (ref "C362") (pin "1") (pinfunction "1_1") (pintype "passive"))
      (node (ref "C363") (pin "1") (pinfunction "1_1") (pintype "passive"))
      (node (ref "C364") (pin "1") (pinfunction "1_1") (pintype "passive"))
      (node (ref "L29") (pin "2") (pinfunction "2_2") (pintype "passive"))
    )
    (net (code "12") (name "VDDA_PLL1") (class "Default")
      (node (ref "C379") (pin "1") (pinfunction "1_1") (pintype "passive"))
      (node (ref "C380") (pin "1") (pinfunction "1_1") (pintype "passive"))
      (node (ref "C381") (pin "1") (pinfunction "1_1") (pintype "passive"))
      (node (ref "L30") (pin "2") (pinfunction "2_2") (pintype "passive"))
    )
    (net (code "13") (name "VDDA_PLL2") (class "Default")
      (node (ref "C395") (pin "1") (pinfunction "1_1") (pintype "passive"))
      (node (ref "C396") (pin "1") (pinfunction "1_1") (pintype "passive"))
      (node (ref "C397") (pin "1") (pinfunction "1_1") (pintype "passive"))
      (node (ref "L31") (pin "2") (pinfunction "2_2") (pintype "passive"))
    )
    (net (code "14") (name "VDDA_SYS_MON") (class "Default")
      (node (ref "R173") (pin "2") (pinfunction "2_2") (pintype "passive"))
      (node (ref "R174") (pin "1") (pinfunction "1_1") (pintype "passive"))
    )
    (net (code "15") (name "VDD_DLL_MMC0") (class "Default")
      (node (ref "C353") (pin "1") (pinfunction "1_1") (pintype "passive"))
      (node (ref "C354") (pin "1") (pinfunction "1_1") (pintype "passive"))
      (node (ref "C355") (pin "1") (pinfunction "1_1") (pintype "passive"))
      (node (ref "L26") (pin "2") (pinfunction "2_2") (pintype "passive"))
    )
  )
)
